# KeyMux40.net
KiCad netlist of a schematic drawn in EAGLE
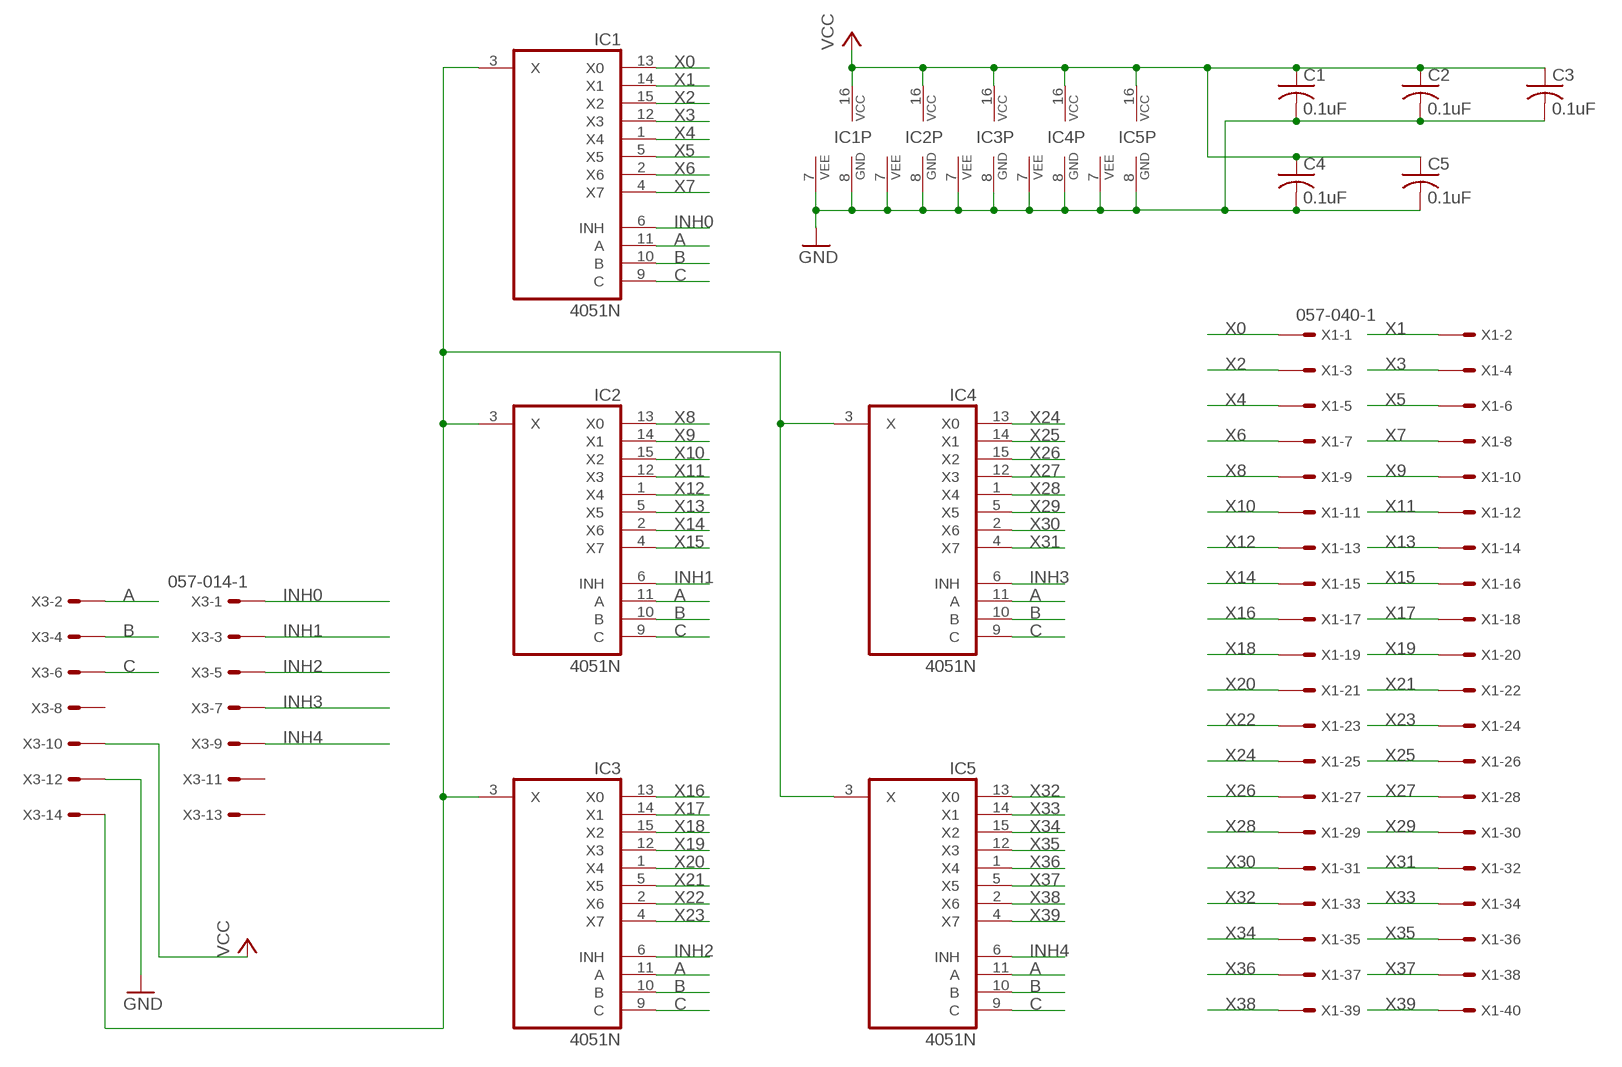
[diagram p0: schematic, sheet 1]

(export (version "E")
  (design (tool "Eeschema 10.0.6"))
  (components
    (comp (ref "C1")
      (value "0.1uF")
      (footprint "eagle-import:C025-025X050")
      (libsource (lib "eagle-import") (part "C-US025-025X050"))
    )
    (comp (ref "C2")
      (value "0.1uF")
      (footprint "eagle-import:C025-025X050")
      (libsource (lib "eagle-import") (part "C-US025-025X050"))
    )
    (comp (ref "C3")
      (value "0.1uF")
      (footprint "eagle-import:C025-025X050")
      (libsource (lib "eagle-import") (part "C-US025-025X050"))
    )
    (comp (ref "C4")
      (value "0.1uF")
      (footprint "eagle-import:C025-025X050")
      (libsource (lib "eagle-import") (part "C-US025-025X050"))
    )
    (comp (ref "C5")
      (value "0.1uF")
      (footprint "eagle-import:C025-025X050")
      (libsource (lib "eagle-import") (part "C-US025-025X050"))
    )
    (comp (ref "IC1")
      (value "4051N")
      (footprint "eagle-import:DIL16")
      (libsource (lib "eagle-import") (part "4051N"))
    )
    (comp (ref "IC2")
      (value "4051N")
      (footprint "eagle-import:DIL16")
      (libsource (lib "eagle-import") (part "4051N"))
    )
    (comp (ref "IC3")
      (value "4051N")
      (footprint "eagle-import:DIL16")
      (libsource (lib "eagle-import") (part "4051N"))
    )
    (comp (ref "IC4")
      (value "4051N")
      (footprint "eagle-import:DIL16")
      (libsource (lib "eagle-import") (part "4051N"))
    )
    (comp (ref "IC5")
      (value "4051N")
      (footprint "eagle-import:DIL16")
      (libsource (lib "eagle-import") (part "4051N"))
    )
    (comp (ref "X1")
      (value "057-040-1")
      (footprint "eagle-import:057-040-1")
      (libsource (lib "eagle-import") (part "057-040-1"))
    )
    (comp (ref "X3")
      (value "057-014-1")
      (footprint "eagle-import:057-014-1")
      (libsource (lib "eagle-import") (part "057-014-1"))
    )
  )
  (nets
    (net (code "1") (name "/A") (class "Default")
      (node (ref "IC1") (pin "11") (pinfunction "A_11") (pintype "input"))
      (node (ref "IC2") (pin "11") (pinfunction "A_11") (pintype "input"))
      (node (ref "IC3") (pin "11") (pinfunction "A_11") (pintype "input"))
      (node (ref "IC4") (pin "11") (pinfunction "A_11") (pintype "input"))
      (node (ref "IC5") (pin "11") (pinfunction "A_11") (pintype "input"))
      (node (ref "X3") (pin "2") (pinfunction "S_2") (pintype "passive"))
    )
    (net (code "2") (name "/B") (class "Default")
      (node (ref "IC1") (pin "10") (pinfunction "B_10") (pintype "input"))
      (node (ref "IC2") (pin "10") (pinfunction "B_10") (pintype "input"))
      (node (ref "IC3") (pin "10") (pinfunction "B_10") (pintype "input"))
      (node (ref "IC4") (pin "10") (pinfunction "B_10") (pintype "input"))
      (node (ref "IC5") (pin "10") (pinfunction "B_10") (pintype "input"))
      (node (ref "X3") (pin "4") (pinfunction "S_4") (pintype "passive"))
    )
    (net (code "3") (name "/C") (class "Default")
      (node (ref "IC1") (pin "9") (pinfunction "C_9") (pintype "input"))
      (node (ref "IC2") (pin "9") (pinfunction "C_9") (pintype "input"))
      (node (ref "IC3") (pin "9") (pinfunction "C_9") (pintype "input"))
      (node (ref "IC4") (pin "9") (pinfunction "C_9") (pintype "input"))
      (node (ref "IC5") (pin "9") (pinfunction "C_9") (pintype "input"))
      (node (ref "X3") (pin "6") (pinfunction "S_6") (pintype "passive"))
    )
    (net (code "4") (name "/INH0") (class "Default")
      (node (ref "IC1") (pin "6") (pinfunction "INH_6") (pintype "input"))
      (node (ref "X3") (pin "1") (pinfunction "S_1") (pintype "passive"))
    )
    (net (code "5") (name "/INH1") (class "Default")
      (node (ref "IC2") (pin "6") (pinfunction "INH_6") (pintype "input"))
      (node (ref "X3") (pin "3") (pinfunction "S_3") (pintype "passive"))
    )
    (net (code "6") (name "/INH2") (class "Default")
      (node (ref "IC3") (pin "6") (pinfunction "INH_6") (pintype "input"))
      (node (ref "X3") (pin "5") (pinfunction "S_5") (pintype "passive"))
    )
    (net (code "7") (name "/INH3") (class "Default")
      (node (ref "IC4") (pin "6") (pinfunction "INH_6") (pintype "input"))
      (node (ref "X3") (pin "7") (pinfunction "S_7") (pintype "passive"))
    )
    (net (code "8") (name "/INH4") (class "Default")
      (node (ref "IC5") (pin "6") (pinfunction "INH_6") (pintype "input"))
      (node (ref "X3") (pin "9") (pinfunction "S_9") (pintype "passive"))
    )
    (net (code "9") (name "/X0") (class "Default")
      (node (ref "IC1") (pin "13") (pinfunction "X0_13") (pintype "bidirectional"))
      (node (ref "X1") (pin "1") (pinfunction "S_1") (pintype "passive"))
    )
    (net (code "10") (name "/X1") (class "Default")
      (node (ref "IC1") (pin "14") (pinfunction "X1_14") (pintype "bidirectional"))
      (node (ref "X1") (pin "2") (pinfunction "S_2") (pintype "passive"))
    )
    (net (code "11") (name "/X2") (class "Default")
      (node (ref "IC1") (pin "15") (pinfunction "X2_15") (pintype "bidirectional"))
      (node (ref "X1") (pin "3") (pinfunction "S_3") (pintype "passive"))
    )
    (net (code "12") (name "/X3") (class "Default")
      (node (ref "IC1") (pin "12") (pinfunction "X3_12") (pintype "bidirectional"))
      (node (ref "X1") (pin "4") (pinfunction "S_4") (pintype "passive"))
    )
    (net (code "13") (name "/X4") (class "Default")
      (node (ref "IC1") (pin "1") (pinfunction "X4_1") (pintype "bidirectional"))
      (node (ref "X1") (pin "5") (pinfunction "S_5") (pintype "passive"))
    )
    (net (code "14") (name "/X5") (class "Default")
      (node (ref "IC1") (pin "5") (pinfunction "X5_5") (pintype "bidirectional"))
      (node (ref "X1") (pin "6") (pinfunction "S_6") (pintype "passive"))
    )
    (net (code "15") (name "/X6") (class "Default")
      (node (ref "IC1") (pin "2") (pinfunction "X6_2") (pintype "bidirectional"))
      (node (ref "X1") (pin "7") (pinfunction "S_7") (pintype "passive"))
    )
    (net (code "16") (name "/X7") (class "Default")
      (node (ref "IC1") (pin "4") (pinfunction "X7_4") (pintype "bidirectional"))
      (node (ref "X1") (pin "8") (pinfunction "S_8") (pintype "passive"))
    )
    (net (code "17") (name "/X8") (class "Default")
      (node (ref "IC2") (pin "13") (pinfunction "X0_13") (pintype "bidirectional"))
      (node (ref "X1") (pin "9") (pinfunction "S_9") (pintype "passive"))
    )
    (net (code "18") (name "/X9") (class "Default")
      (node (ref "IC2") (pin "14") (pinfunction "X1_14") (pintype "bidirectional"))
      (node (ref "X1") (pin "10") (pinfunction "S_10") (pintype "passive"))
    )
    (net (code "19") (name "/X10") (class "Default")
      (node (ref "IC2") (pin "15") (pinfunction "X2_15") (pintype "bidirectional"))
      (node (ref "X1") (pin "11") (pinfunction "S_11") (pintype "passive"))
    )
    (net (code "20") (name "/X11") (class "Default")
      (node (ref "IC2") (pin "12") (pinfunction "X3_12") (pintype "bidirectional"))
      (node (ref "X1") (pin "12") (pinfunction "S_12") (pintype "passive"))
    )
    (net (code "21") (name "/X12") (class "Default")
      (node (ref "IC2") (pin "1") (pinfunction "X4_1") (pintype "bidirectional"))
      (node (ref "X1") (pin "13") (pinfunction "S_13") (pintype "passive"))
    )
    (net (code "22") (name "/X13") (class "Default")
      (node (ref "IC2") (pin "5") (pinfunction "X5_5") (pintype "bidirectional"))
      (node (ref "X1") (pin "14") (pinfunction "S_14") (pintype "passive"))
    )
    (net (code "23") (name "/X14") (class "Default")
      (node (ref "IC2") (pin "2") (pinfunction "X6_2") (pintype "bidirectional"))
      (node (ref "X1") (pin "15") (pinfunction "S_15") (pintype "passive"))
    )
    (net (code "24") (name "/X15") (class "Default")
      (node (ref "IC2") (pin "4") (pinfunction "X7_4") (pintype "bidirectional"))
      (node (ref "X1") (pin "16") (pinfunction "S_16") (pintype "passive"))
    )
    (net (code "25") (name "/X16") (class "Default")
      (node (ref "IC3") (pin "13") (pinfunction "X0_13") (pintype "bidirectional"))
      (node (ref "X1") (pin "17") (pinfunction "S_17") (pintype "passive"))
    )
    (net (code "26") (name "/X17") (class "Default")
      (node (ref "IC3") (pin "14") (pinfunction "X1_14") (pintype "bidirectional"))
      (node (ref "X1") (pin "18") (pinfunction "S_18") (pintype "passive"))
    )
    (net (code "27") (name "/X18") (class "Default")
      (node (ref "IC3") (pin "15") (pinfunction "X2_15") (pintype "bidirectional"))
      (node (ref "X1") (pin "19") (pinfunction "S_19") (pintype "passive"))
    )
    (net (code "28") (name "/X19") (class "Default")
      (node (ref "IC3") (pin "12") (pinfunction "X3_12") (pintype "bidirectional"))
      (node (ref "X1") (pin "20") (pinfunction "S_20") (pintype "passive"))
    )
    (net (code "29") (name "/X20") (class "Default")
      (node (ref "IC3") (pin "1") (pinfunction "X4_1") (pintype "bidirectional"))
      (node (ref "X1") (pin "21") (pinfunction "S_21") (pintype "passive"))
    )
    (net (code "30") (name "/X21") (class "Default")
      (node (ref "IC3") (pin "5") (pinfunction "X5_5") (pintype "bidirectional"))
      (node (ref "X1") (pin "22") (pinfunction "S_22") (pintype "passive"))
    )
    (net (code "31") (name "/X22") (class "Default")
      (node (ref "IC3") (pin "2") (pinfunction "X6_2") (pintype "bidirectional"))
      (node (ref "X1") (pin "23") (pinfunction "S_23") (pintype "passive"))
    )
    (net (code "32") (name "/X23") (class "Default")
      (node (ref "IC3") (pin "4") (pinfunction "X7_4") (pintype "bidirectional"))
      (node (ref "X1") (pin "24") (pinfunction "S_24") (pintype "passive"))
    )
    (net (code "33") (name "/X24") (class "Default")
      (node (ref "IC4") (pin "13") (pinfunction "X0_13") (pintype "bidirectional"))
      (node (ref "X1") (pin "25") (pinfunction "S_25") (pintype "passive"))
    )
    (net (code "34") (name "/X25") (class "Default")
      (node (ref "IC4") (pin "14") (pinfunction "X1_14") (pintype "bidirectional"))
      (node (ref "X1") (pin "26") (pinfunction "S_26") (pintype "passive"))
    )
    (net (code "35") (name "/X26") (class "Default")
      (node (ref "IC4") (pin "15") (pinfunction "X2_15") (pintype "bidirectional"))
      (node (ref "X1") (pin "27") (pinfunction "S_27") (pintype "passive"))
    )
    (net (code "36") (name "/X27") (class "Default")
      (node (ref "IC4") (pin "12") (pinfunction "X3_12") (pintype "bidirectional"))
      (node (ref "X1") (pin "28") (pinfunction "S_28") (pintype "passive"))
    )
    (net (code "37") (name "/X28") (class "Default")
      (node (ref "IC4") (pin "1") (pinfunction "X4_1") (pintype "bidirectional"))
      (node (ref "X1") (pin "29") (pinfunction "S_29") (pintype "passive"))
    )
    (net (code "38") (name "/X29") (class "Default")
      (node (ref "IC4") (pin "5") (pinfunction "X5_5") (pintype "bidirectional"))
      (node (ref "X1") (pin "30") (pinfunction "S_30") (pintype "passive"))
    )
    (net (code "39") (name "/X30") (class "Default")
      (node (ref "IC4") (pin "2") (pinfunction "X6_2") (pintype "bidirectional"))
      (node (ref "X1") (pin "31") (pinfunction "S_31") (pintype "passive"))
    )
    (net (code "40") (name "/X31") (class "Default")
      (node (ref "IC4") (pin "4") (pinfunction "X7_4") (pintype "bidirectional"))
      (node (ref "X1") (pin "32") (pinfunction "S_32") (pintype "passive"))
    )
    (net (code "41") (name "/X32") (class "Default")
      (node (ref "IC5") (pin "13") (pinfunction "X0_13") (pintype "bidirectional"))
      (node (ref "X1") (pin "33") (pinfunction "S_33") (pintype "passive"))
    )
    (net (code "42") (name "/X33") (class "Default")
      (node (ref "IC5") (pin "14") (pinfunction "X1_14") (pintype "bidirectional"))
      (node (ref "X1") (pin "34") (pinfunction "S_34") (pintype "passive"))
    )
    (net (code "43") (name "/X34") (class "Default")
      (node (ref "IC5") (pin "15") (pinfunction "X2_15") (pintype "bidirectional"))
      (node (ref "X1") (pin "35") (pinfunction "S_35") (pintype "passive"))
    )
    (net (code "44") (name "/X35") (class "Default")
      (node (ref "IC5") (pin "12") (pinfunction "X3_12") (pintype "bidirectional"))
      (node (ref "X1") (pin "36") (pinfunction "S_36") (pintype "passive"))
    )
    (net (code "45") (name "/X36") (class "Default")
      (node (ref "IC5") (pin "1") (pinfunction "X4_1") (pintype "bidirectional"))
      (node (ref "X1") (pin "37") (pinfunction "S_37") (pintype "passive"))
    )
    (net (code "46") (name "/X37") (class "Default")
      (node (ref "IC5") (pin "5") (pinfunction "X5_5") (pintype "bidirectional"))
      (node (ref "X1") (pin "38") (pinfunction "S_38") (pintype "passive"))
    )
    (net (code "47") (name "/X38") (class "Default")
      (node (ref "IC5") (pin "2") (pinfunction "X6_2") (pintype "bidirectional"))
      (node (ref "X1") (pin "39") (pinfunction "S_39") (pintype "passive"))
    )
    (net (code "48") (name "/X39") (class "Default")
      (node (ref "IC5") (pin "4") (pinfunction "X7_4") (pintype "bidirectional"))
      (node (ref "X1") (pin "40") (pinfunction "S_40") (pintype "passive"))
    )
    (net (code "49") (name "GND") (class "Default")
      (node (ref "C1") (pin "2") (pinfunction "2_2") (pintype "passive"))
      (node (ref "C2") (pin "2") (pinfunction "2_2") (pintype "passive"))
      (node (ref "C3") (pin "2") (pinfunction "2_2") (pintype "passive"))
      (node (ref "C4") (pin "2") (pinfunction "2_2") (pintype "passive"))
      (node (ref "C5") (pin "2") (pinfunction "2_2") (pintype "passive"))
      (node (ref "IC1") (pin "7") (pinfunction "VEE_7") (pintype "power_in"))
      (node (ref "IC1") (pin "8") (pinfunction "GND_8") (pintype "power_in"))
      (node (ref "IC2") (pin "7") (pinfunction "VEE_7") (pintype "power_in"))
      (node (ref "IC2") (pin "8") (pinfunction "GND_8") (pintype "power_in"))
      (node (ref "IC3") (pin "7") (pinfunction "VEE_7") (pintype "power_in"))
      (node (ref "IC3") (pin "8") (pinfunction "GND_8") (pintype "power_in"))
      (node (ref "IC4") (pin "7") (pinfunction "VEE_7") (pintype "power_in"))
      (node (ref "IC4") (pin "8") (pinfunction "GND_8") (pintype "power_in"))
      (node (ref "IC5") (pin "7") (pinfunction "VEE_7") (pintype "power_in"))
      (node (ref "IC5") (pin "8") (pinfunction "GND_8") (pintype "power_in"))
      (node (ref "X3") (pin "12") (pinfunction "S_12") (pintype "passive"))
    )
    (net (code "50") (name "Net-(IC1A-X)") (class "Default")
      (node (ref "IC1") (pin "3") (pinfunction "X_3") (pintype "bidirectional"))
      (node (ref "IC2") (pin "3") (pinfunction "X_3") (pintype "bidirectional"))
      (node (ref "IC3") (pin "3") (pinfunction "X_3") (pintype "bidirectional"))
      (node (ref "IC4") (pin "3") (pinfunction "X_3") (pintype "bidirectional"))
      (node (ref "IC5") (pin "3") (pinfunction "X_3") (pintype "bidirectional"))
      (node (ref "X3") (pin "14") (pinfunction "S_14") (pintype "passive"))
    )
    (net (code "51") (name "VCC") (class "Default")
      (node (ref "C1") (pin "1") (pinfunction "1_1") (pintype "passive"))
      (node (ref "C2") (pin "1") (pinfunction "1_1") (pintype "passive"))
      (node (ref "C3") (pin "1") (pinfunction "1_1") (pintype "passive"))
      (node (ref "C4") (pin "1") (pinfunction "1_1") (pintype "passive"))
      (node (ref "C5") (pin "1") (pinfunction "1_1") (pintype "passive"))
      (node (ref "IC1") (pin "16") (pinfunction "VCC_16") (pintype "power_in"))
      (node (ref "IC2") (pin "16") (pinfunction "VCC_16") (pintype "power_in"))
      (node (ref "IC3") (pin "16") (pinfunction "VCC_16") (pintype "power_in"))
      (node (ref "IC4") (pin "16") (pinfunction "VCC_16") (pintype "power_in"))
      (node (ref "IC5") (pin "16") (pinfunction "VCC_16") (pintype "power_in"))
      (node (ref "X3") (pin "10") (pinfunction "S_10") (pintype "passive"))
    )
    (net (code "52") (name "unconnected-(X3C-S-Pad11)") (class "Default")
      (node (ref "X3") (pin "11") (pinfunction "S_11") (pintype "passive"))
    )
    (net (code "53") (name "unconnected-(X3E-S-Pad13)") (class "Default")
      (node (ref "X3") (pin "13") (pinfunction "S_13") (pintype "passive"))
    )
    (net (code "54") (name "unconnected-(X3M-S-Pad8)") (class "Default")
      (node (ref "X3") (pin "8") (pinfunction "S_8") (pintype "passive"))
    )
  )
)
